# mcu.net
KiCad netlist of a schematic drawn in Altium Designer
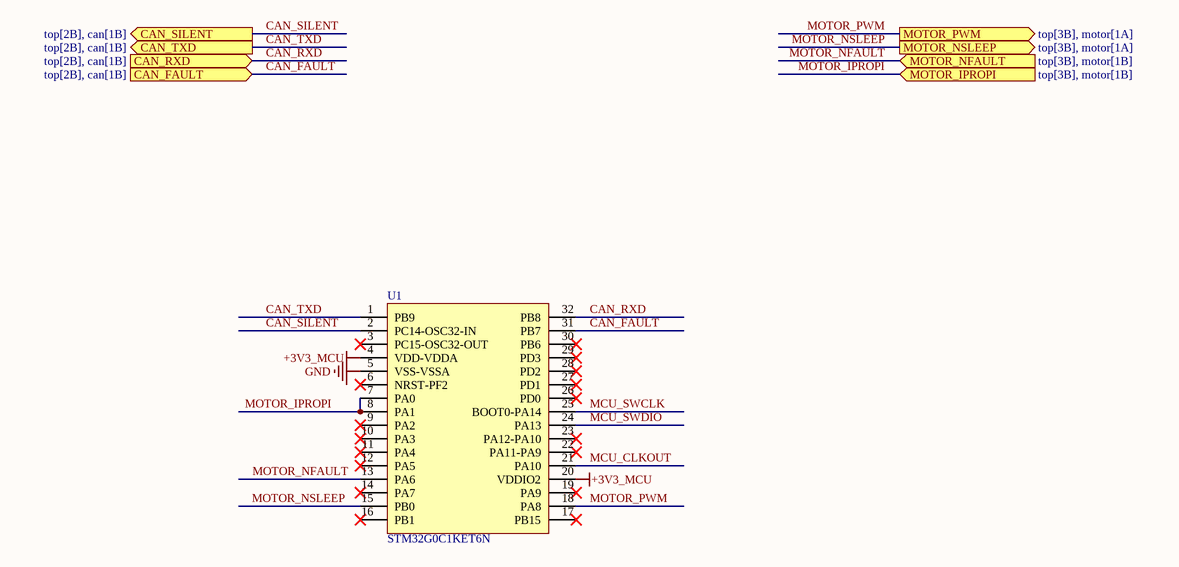
[diagram p0: mcu.SchDoc]

(export (version "E")
  (design (tool "Eeschema 10.0.6"))
  (components
    (comp (ref "U1")
      (value "STM32G0C1KET6N")
      (footprint "STM32G0C1KET6N")
      (description "STM32 MCU")
      (libsource (lib "altium_library") (part "STM32G0C1KET6N"))
    )
  )
  (nets
    (net (code "1") (name "+3V3_MCU") (class "Default")
      (node (ref "U1") (pin "20") (pinfunction "VDDIO2_20") (pintype "passive"))
      (node (ref "U1") (pin "4") (pinfunction "VDD-VDDA_4") (pintype "passive"))
    )
    (net (code "2") (name "/CAN_FAULT") (class "Default")
      (node (ref "U1") (pin "31") (pinfunction "PB7_31") (pintype "passive"))
    )
    (net (code "3") (name "/CAN_RXD") (class "Default")
      (node (ref "U1") (pin "32") (pinfunction "PB8_32") (pintype "passive"))
    )
    (net (code "4") (name "/CAN_SILENT") (class "Default")
      (node (ref "U1") (pin "2") (pinfunction "PC14-OSC32-IN_2") (pintype "passive"))
    )
    (net (code "5") (name "/CAN_TXD") (class "Default")
      (node (ref "U1") (pin "1") (pinfunction "PB9_1") (pintype "passive"))
    )
    (net (code "6") (name "/MCU_CLKOUT") (class "Default")
      (node (ref "U1") (pin "21") (pinfunction "PA10_21") (pintype "passive"))
    )
    (net (code "7") (name "/MCU_SWCLK") (class "Default")
      (node (ref "U1") (pin "25") (pinfunction "BOOT0-PA14_25") (pintype "passive"))
    )
    (net (code "8") (name "/MCU_SWDIO") (class "Default")
      (node (ref "U1") (pin "24") (pinfunction "PA13_24") (pintype "passive"))
    )
    (net (code "9") (name "/MOTOR_IPROPI") (class "Default")
      (node (ref "U1") (pin "7") (pinfunction "PA0_7") (pintype "passive"))
      (node (ref "U1") (pin "8") (pinfunction "PA1_8") (pintype "passive"))
    )
    (net (code "10") (name "/MOTOR_NFAULT") (class "Default")
      (node (ref "U1") (pin "13") (pinfunction "PA6_13") (pintype "passive"))
    )
    (net (code "11") (name "/MOTOR_NSLEEP") (class "Default")
      (node (ref "U1") (pin "15") (pinfunction "PB0_15") (pintype "passive"))
    )
    (net (code "12") (name "/MOTOR_PWM") (class "Default")
      (node (ref "U1") (pin "18") (pinfunction "PA8_18") (pintype "passive"))
    )
    (net (code "13") (name "GND") (class "Default")
      (node (ref "U1") (pin "5") (pinfunction "VSS-VSSA_5") (pintype "passive"))
    )
    (net (code "14") (name "unconnected-(U1-NRST-PF2-Pad6)") (class "Default")
      (node (ref "U1") (pin "6") (pinfunction "NRST-PF2_6") (pintype "passive+no_connect"))
    )
    (net (code "15") (name "unconnected-(U1-PA2-Pad9)") (class "Default")
      (node (ref "U1") (pin "9") (pinfunction "PA2_9") (pintype "passive+no_connect"))
    )
    (net (code "16") (name "unconnected-(U1-PA3-Pad10)") (class "Default")
      (node (ref "U1") (pin "10") (pinfunction "PA3_10") (pintype "passive+no_connect"))
    )
    (net (code "17") (name "unconnected-(U1-PA4-Pad11)") (class "Default")
      (node (ref "U1") (pin "11") (pinfunction "PA4_11") (pintype "passive+no_connect"))
    )
    (net (code "18") (name "unconnected-(U1-PA5-Pad12)") (class "Default")
      (node (ref "U1") (pin "12") (pinfunction "PA5_12") (pintype "passive+no_connect"))
    )
    (net (code "19") (name "unconnected-(U1-PA7-Pad14)") (class "Default")
      (node (ref "U1") (pin "14") (pinfunction "PA7_14") (pintype "passive+no_connect"))
    )
    (net (code "20") (name "unconnected-(U1-PA9-Pad19)") (class "Default")
      (node (ref "U1") (pin "19") (pinfunction "PA9_19") (pintype "passive+no_connect"))
    )
    (net (code "21") (name "unconnected-(U1-PA11-PA9-Pad22)") (class "Default")
      (node (ref "U1") (pin "22") (pinfunction "PA11-PA9_22") (pintype "passive+no_connect"))
    )
    (net (code "22") (name "unconnected-(U1-PA12-PA10-Pad23)") (class "Default")
      (node (ref "U1") (pin "23") (pinfunction "PA12-PA10_23") (pintype "passive+no_connect"))
    )
    (net (code "23") (name "unconnected-(U1-PB1-Pad16)") (class "Default")
      (node (ref "U1") (pin "16") (pinfunction "PB1_16") (pintype "passive+no_connect"))
    )
    (net (code "24") (name "unconnected-(U1-PB6-Pad30)") (class "Default")
      (node (ref "U1") (pin "30") (pinfunction "PB6_30") (pintype "passive+no_connect"))
    )
    (net (code "25") (name "unconnected-(U1-PB15-Pad17)") (class "Default")
      (node (ref "U1") (pin "17") (pinfunction "PB15_17") (pintype "passive+no_connect"))
    )
    (net (code "26") (name "unconnected-(U1-PC15-OSC32-OUT-Pad3)") (class "Default")
      (node (ref "U1") (pin "3") (pinfunction "PC15-OSC32-OUT_3") (pintype "passive+no_connect"))
    )
    (net (code "27") (name "unconnected-(U1-PD0-Pad26)") (class "Default")
      (node (ref "U1") (pin "26") (pinfunction "PD0_26") (pintype "passive+no_connect"))
    )
    (net (code "28") (name "unconnected-(U1-PD1-Pad27)") (class "Default")
      (node (ref "U1") (pin "27") (pinfunction "PD1_27") (pintype "passive+no_connect"))
    )
    (net (code "29") (name "unconnected-(U1-PD2-Pad28)") (class "Default")
      (node (ref "U1") (pin "28") (pinfunction "PD2_28") (pintype "passive+no_connect"))
    )
    (net (code "30") (name "unconnected-(U1-PD3-Pad29)") (class "Default")
      (node (ref "U1") (pin "29") (pinfunction "PD3_29") (pintype "passive+no_connect"))
    )
  )
)
